# booster.net
KiCad netlist of a schematic drawn in EAGLE
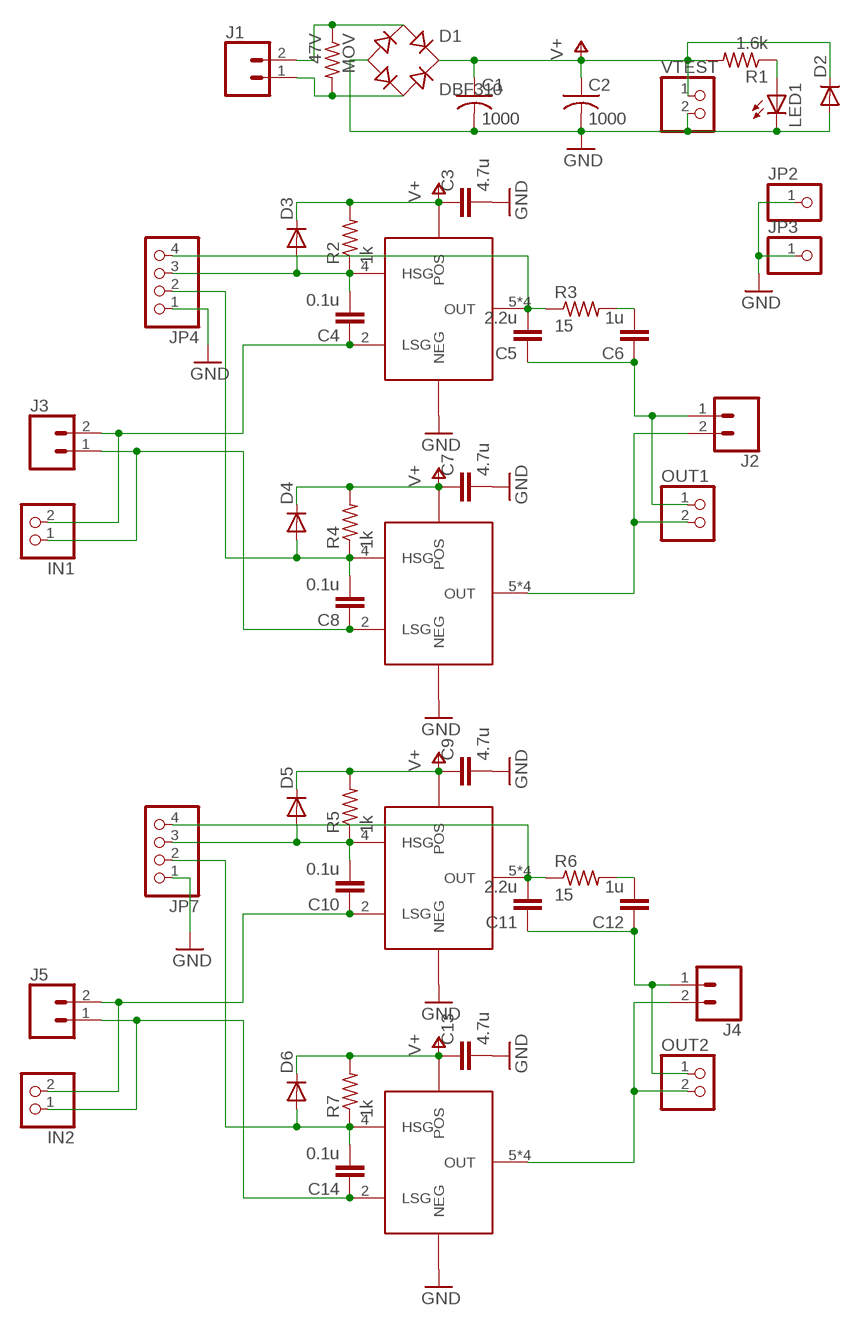
[diagram p0: schematic, sheet 1]

(export (version "E")
  (design (tool "Eeschema 10.0.6"))
  (components
    (comp (ref "C1")
      (value "1000")
      (footprint "eagle-import:CAPPRD500W65D1250H2500B")
      (libsource (lib "eagle-import") (part "UVY1H102MHD"))
    )
    (comp (ref "C2")
      (value "1000")
      (footprint "eagle-import:CAPPRD500W65D1250H2500B")
      (libsource (lib "eagle-import") (part "UVY1H102MHD"))
    )
    (comp (ref "C3")
      (value "4.7u")
      (footprint "eagle-import:C1206")
      (libsource (lib "eagle-import") (part "C-EUC1206"))
    )
    (comp (ref "C4")
      (value "0.1u")
      (footprint "eagle-import:C1206")
      (libsource (lib "eagle-import") (part "C-EUC1206"))
    )
    (comp (ref "C5")
      (value "2.2u")
      (footprint "eagle-import:C1206")
      (libsource (lib "eagle-import") (part "C-EUC1206"))
    )
    (comp (ref "C6")
      (value "1u")
      (footprint "eagle-import:C1206")
      (libsource (lib "eagle-import") (part "C-EUC1206"))
    )
    (comp (ref "C7")
      (value "4.7u")
      (footprint "eagle-import:C1206")
      (libsource (lib "eagle-import") (part "C-EUC1206"))
    )
    (comp (ref "C8")
      (value "0.1u")
      (footprint "eagle-import:C1206")
      (libsource (lib "eagle-import") (part "C-EUC1206"))
    )
    (comp (ref "C9")
      (value "4.7u")
      (footprint "eagle-import:C1206")
      (libsource (lib "eagle-import") (part "C-EUC1206"))
    )
    (comp (ref "C10")
      (value "0.1u")
      (footprint "eagle-import:C1206")
      (libsource (lib "eagle-import") (part "C-EUC1206"))
    )
    (comp (ref "C11")
      (value "2.2u")
      (footprint "eagle-import:C1206")
      (libsource (lib "eagle-import") (part "C-EUC1206"))
    )
    (comp (ref "C12")
      (value "1u")
      (footprint "eagle-import:C1206")
      (libsource (lib "eagle-import") (part "C-EUC1206"))
    )
    (comp (ref "C13")
      (value "4.7u")
      (footprint "eagle-import:C1206")
      (libsource (lib "eagle-import") (part "C-EUC1206"))
    )
    (comp (ref "C14")
      (value "0.1u")
      (footprint "eagle-import:C1206")
      (libsource (lib "eagle-import") (part "C-EUC1206"))
    )
    (comp (ref "D1")
      (value "DBF310")
      (footprint "eagle-import:4-SMD")
      (libsource (lib "eagle-import") (part "DBF310"))
    )
    (comp (ref "D2")
      (value "DIODE-SMB")
      (footprint "eagle-import:SMB")
      (libsource (lib "eagle-import") (part "DIODE-SMB"))
    )
    (comp (ref "D3")
      (value "DIODE-SMB")
      (footprint "eagle-import:SMB")
      (libsource (lib "eagle-import") (part "DIODE-SMB"))
    )
    (comp (ref "D4")
      (value "DIODE-SMB")
      (footprint "eagle-import:SMB")
      (libsource (lib "eagle-import") (part "DIODE-SMB"))
    )
    (comp (ref "D5")
      (value "DIODE-SMB")
      (footprint "eagle-import:SMB")
      (libsource (lib "eagle-import") (part "DIODE-SMB"))
    )
    (comp (ref "D6")
      (value "DIODE-SMB")
      (footprint "eagle-import:SMB")
      (libsource (lib "eagle-import") (part "DIODE-SMB"))
    )
    (comp (ref "IN1")
      (value "PINHD-1X2")
      (footprint "eagle-import:1X02")
      (libsource (lib "eagle-import") (part "PINHD-1X2"))
    )
    (comp (ref "IN2")
      (value "PINHD-1X2")
      (footprint "eagle-import:1X02")
      (libsource (lib "eagle-import") (part "PINHD-1X2"))
    )
    (comp (ref "J1")
      (value "CONN_025MM")
      (footprint "eagle-import:SCREWTERMINAL-5MM-2")
      (libsource (lib "eagle-import") (part "CONN_025MM"))
    )
    (comp (ref "J2")
      (value "CONN_025MM")
      (footprint "eagle-import:SCREWTERMINAL-5MM-2")
      (libsource (lib "eagle-import") (part "CONN_025MM"))
    )
    (comp (ref "J3")
      (value "CONN_025MM")
      (footprint "eagle-import:SCREWTERMINAL-5MM-2")
      (libsource (lib "eagle-import") (part "CONN_025MM"))
    )
    (comp (ref "J4")
      (value "CONN_025MM")
      (footprint "eagle-import:SCREWTERMINAL-5MM-2")
      (libsource (lib "eagle-import") (part "CONN_025MM"))
    )
    (comp (ref "J5")
      (value "CONN_025MM")
      (footprint "eagle-import:SCREWTERMINAL-5MM-2")
      (libsource (lib "eagle-import") (part "CONN_025MM"))
    )
    (comp (ref "JP2")
      (value "PINHD-1X1")
      (footprint "eagle-import:1X01")
      (libsource (lib "eagle-import") (part "PINHD-1X1"))
    )
    (comp (ref "JP3")
      (value "PINHD-1X1")
      (footprint "eagle-import:1X01")
      (libsource (lib "eagle-import") (part "PINHD-1X1"))
    )
    (comp (ref "JP4")
      (value "PINHD-1X4")
      (footprint "eagle-import:1X04")
      (libsource (lib "eagle-import") (part "PINHD-1X4"))
    )
    (comp (ref "JP7")
      (value "PINHD-1X4")
      (footprint "eagle-import:1X04")
      (libsource (lib "eagle-import") (part "PINHD-1X4"))
    )
    (comp (ref "LED1")
      (value "LED5MM")
      (footprint "eagle-import:LED5MM")
      (libsource (lib "eagle-import") (part "LED5MM"))
    )
    (comp (ref "MOV")
      (value "47V")
      (footprint "eagle-import:R1206")
      (libsource (lib "eagle-import") (part "R-US_R1206"))
    )
    (comp (ref "OUT1")
      (value "PINHD-1X2")
      (footprint "eagle-import:1X02")
      (libsource (lib "eagle-import") (part "PINHD-1X2"))
    )
    (comp (ref "OUT2")
      (value "PINHD-1X2")
      (footprint "eagle-import:1X02")
      (libsource (lib "eagle-import") (part "PINHD-1X2"))
    )
    (comp (ref "R1")
      (value "1.6k")
      (footprint "eagle-import:R2512")
      (libsource (lib "eagle-import") (part "R-US_R2512"))
    )
    (comp (ref "R2")
      (value "1k")
      (footprint "eagle-import:R1206")
      (libsource (lib "eagle-import") (part "R-US_R1206"))
    )
    (comp (ref "R3")
      (value "15")
      (footprint "eagle-import:R1206")
      (libsource (lib "eagle-import") (part "R-US_R1206"))
    )
    (comp (ref "R4")
      (value "1k")
      (footprint "eagle-import:R1206")
      (libsource (lib "eagle-import") (part "R-US_R1206"))
    )
    (comp (ref "R5")
      (value "1k")
      (footprint "eagle-import:R1206")
      (libsource (lib "eagle-import") (part "R-US_R1206"))
    )
    (comp (ref "R6")
      (value "15")
      (footprint "eagle-import:R1206")
      (libsource (lib "eagle-import") (part "R-US_R1206"))
    )
    (comp (ref "R7")
      (value "1k")
      (footprint "eagle-import:R1206")
      (libsource (lib "eagle-import") (part "R-US_R1206"))
    )
    (comp (ref "U1")
      (value "SI4554DY")
      (footprint "eagle-import:SOIC-8")
      (libsource (lib "eagle-import") (part "SI4554DY"))
    )
    (comp (ref "U2")
      (value "SI4554DY")
      (footprint "eagle-import:SOIC-8")
      (libsource (lib "eagle-import") (part "SI4554DY"))
    )
    (comp (ref "U3")
      (value "SI4554DY")
      (footprint "eagle-import:SOIC-8")
      (libsource (lib "eagle-import") (part "SI4554DY"))
    )
    (comp (ref "U4")
      (value "SI4554DY")
      (footprint "eagle-import:SOIC-8")
      (libsource (lib "eagle-import") (part "SI4554DY"))
    )
    (comp (ref "VTEST")
      (value "PINHD-1X2")
      (footprint "eagle-import:1X02")
      (libsource (lib "eagle-import") (part "PINHD-1X2"))
    )
  )
  (nets
    (net (code "1") (name "GND") (class "Default")
      (node (ref "C1") (pin "2") (pinfunction "2_2") (pintype "passive"))
      (node (ref "C13") (pin "2") (pinfunction "2_2") (pintype "passive"))
      (node (ref "C2") (pin "2") (pinfunction "2_2") (pintype "passive"))
      (node (ref "C3") (pin "2") (pinfunction "2_2") (pintype "passive"))
      (node (ref "C7") (pin "2") (pinfunction "2_2") (pintype "passive"))
      (node (ref "C9") (pin "2") (pinfunction "2_2") (pintype "passive"))
      (node (ref "D1") (pin "-") (pinfunction "-_-") (pintype "passive"))
      (node (ref "D2") (pin "A") (pinfunction "A_A") (pintype "passive"))
      (node (ref "JP2") (pin "1") (pinfunction "1_1") (pintype "passive"))
      (node (ref "JP3") (pin "1") (pinfunction "1_1") (pintype "passive"))
      (node (ref "JP4") (pin "1") (pinfunction "1_1") (pintype "passive"))
      (node (ref "JP7") (pin "1") (pinfunction "1_1") (pintype "passive"))
      (node (ref "LED1") (pin "K") (pinfunction "C_K") (pintype "passive"))
      (node (ref "U1") (pin "1") (pinfunction "NEG_1") (pintype "bidirectional"))
      (node (ref "U2") (pin "1") (pinfunction "NEG_1") (pintype "bidirectional"))
      (node (ref "U3") (pin "1") (pinfunction "NEG_1") (pintype "bidirectional"))
      (node (ref "U4") (pin "1") (pinfunction "NEG_1") (pintype "bidirectional"))
      (node (ref "VTEST") (pin "2") (pinfunction "2_2") (pintype "passive"))
    )
    (net (code "2") (name "Net-(C5-Pad1)") (class "Default")
      (node (ref "C5") (pin "1") (pinfunction "1_1") (pintype "passive"))
      (node (ref "C6") (pin "1") (pinfunction "1_1") (pintype "passive"))
      (node (ref "J2") (pin "1") (pinfunction "1_1") (pintype "passive"))
      (node (ref "OUT1") (pin "1") (pinfunction "1_1") (pintype "passive"))
    )
    (net (code "3") (name "Net-(C5-Pad2)") (class "Default")
      (node (ref "C5") (pin "2") (pinfunction "2_2") (pintype "passive"))
      (node (ref "JP4") (pin "4") (pinfunction "4_4") (pintype "passive"))
      (node (ref "R3") (pin "1") (pinfunction "1_1") (pintype "passive"))
      (node (ref "U1") (pin "5") (pinfunction "OUT_5") (pintype "bidirectional"))
      (node (ref "U1") (pin "6") (pinfunction "OUT_6") (pintype "bidirectional"))
      (node (ref "U1") (pin "7") (pinfunction "OUT_7") (pintype "bidirectional"))
      (node (ref "U1") (pin "8") (pinfunction "OUT_8") (pintype "bidirectional"))
    )
    (net (code "4") (name "Net-(C6-Pad2)") (class "Default")
      (node (ref "C6") (pin "2") (pinfunction "2_2") (pintype "passive"))
      (node (ref "R3") (pin "2") (pinfunction "2_2") (pintype "passive"))
    )
    (net (code "5") (name "Net-(C11-Pad1)") (class "Default")
      (node (ref "C11") (pin "1") (pinfunction "1_1") (pintype "passive"))
      (node (ref "C12") (pin "1") (pinfunction "1_1") (pintype "passive"))
      (node (ref "J4") (pin "1") (pinfunction "1_1") (pintype "passive"))
      (node (ref "OUT2") (pin "1") (pinfunction "1_1") (pintype "passive"))
    )
    (net (code "6") (name "Net-(C11-Pad2)") (class "Default")
      (node (ref "C11") (pin "2") (pinfunction "2_2") (pintype "passive"))
      (node (ref "JP7") (pin "4") (pinfunction "4_4") (pintype "passive"))
      (node (ref "R6") (pin "1") (pinfunction "1_1") (pintype "passive"))
      (node (ref "U3") (pin "5") (pinfunction "OUT_5") (pintype "bidirectional"))
      (node (ref "U3") (pin "6") (pinfunction "OUT_6") (pintype "bidirectional"))
      (node (ref "U3") (pin "7") (pinfunction "OUT_7") (pintype "bidirectional"))
      (node (ref "U3") (pin "8") (pinfunction "OUT_8") (pintype "bidirectional"))
    )
    (net (code "7") (name "Net-(C12-Pad2)") (class "Default")
      (node (ref "C12") (pin "2") (pinfunction "2_2") (pintype "passive"))
      (node (ref "R6") (pin "2") (pinfunction "2_2") (pintype "passive"))
    )
    (net (code "8") (name "Net-(D1-AC1)") (class "Default")
      (node (ref "D1") (pin "~1") (pinfunction "AC1_~1") (pintype "passive"))
      (node (ref "J1") (pin "2") (pinfunction "2_2") (pintype "passive"))
      (node (ref "MOV") (pin "1") (pinfunction "1_1") (pintype "passive"))
    )
    (net (code "9") (name "Net-(D1-AC2)") (class "Default")
      (node (ref "D1") (pin "~2") (pinfunction "AC2_~2") (pintype "passive"))
      (node (ref "J1") (pin "1") (pinfunction "1_1") (pintype "passive"))
      (node (ref "MOV") (pin "2") (pinfunction "2_2") (pintype "passive"))
    )
    (net (code "10") (name "Net-(J2-Pad2)") (class "Default")
      (node (ref "J2") (pin "2") (pinfunction "2_2") (pintype "passive"))
      (node (ref "OUT1") (pin "2") (pinfunction "2_2") (pintype "passive"))
      (node (ref "U2") (pin "5") (pinfunction "OUT_5") (pintype "bidirectional"))
      (node (ref "U2") (pin "6") (pinfunction "OUT_6") (pintype "bidirectional"))
      (node (ref "U2") (pin "7") (pinfunction "OUT_7") (pintype "bidirectional"))
      (node (ref "U2") (pin "8") (pinfunction "OUT_8") (pintype "bidirectional"))
    )
    (net (code "11") (name "Net-(J4-Pad2)") (class "Default")
      (node (ref "J4") (pin "2") (pinfunction "2_2") (pintype "passive"))
      (node (ref "OUT2") (pin "2") (pinfunction "2_2") (pintype "passive"))
      (node (ref "U4") (pin "5") (pinfunction "OUT_5") (pintype "bidirectional"))
      (node (ref "U4") (pin "6") (pinfunction "OUT_6") (pintype "bidirectional"))
      (node (ref "U4") (pin "7") (pinfunction "OUT_7") (pintype "bidirectional"))
      (node (ref "U4") (pin "8") (pinfunction "OUT_8") (pintype "bidirectional"))
    )
    (net (code "12") (name "Net-(LED1-PadA)") (class "Default")
      (node (ref "LED1") (pin "A") (pinfunction "A_A") (pintype "passive"))
      (node (ref "R1") (pin "1") (pinfunction "1_1") (pintype "passive"))
    )
    (net (code "13") (name "Net-(U1-HSG)") (class "Default")
      (node (ref "C4") (pin "2") (pinfunction "2_2") (pintype "passive"))
      (node (ref "D3") (pin "A") (pinfunction "A_A") (pintype "passive"))
      (node (ref "JP4") (pin "3") (pinfunction "3_3") (pintype "passive"))
      (node (ref "R2") (pin "1") (pinfunction "1_1") (pintype "passive"))
      (node (ref "U1") (pin "4") (pinfunction "HSG_4") (pintype "bidirectional"))
    )
    (net (code "14") (name "Net-(U1-LSG)") (class "Default")
      (node (ref "C4") (pin "1") (pinfunction "1_1") (pintype "passive"))
      (node (ref "IN1") (pin "2") (pinfunction "2_2") (pintype "passive"))
      (node (ref "J3") (pin "2") (pinfunction "2_2") (pintype "passive"))
      (node (ref "U1") (pin "2") (pinfunction "LSG_2") (pintype "bidirectional"))
    )
    (net (code "15") (name "Net-(U2-HSG)") (class "Default")
      (node (ref "C8") (pin "2") (pinfunction "2_2") (pintype "passive"))
      (node (ref "D4") (pin "A") (pinfunction "A_A") (pintype "passive"))
      (node (ref "JP4") (pin "2") (pinfunction "2_2") (pintype "passive"))
      (node (ref "R4") (pin "1") (pinfunction "1_1") (pintype "passive"))
      (node (ref "U2") (pin "4") (pinfunction "HSG_4") (pintype "bidirectional"))
    )
    (net (code "16") (name "Net-(U2-LSG)") (class "Default")
      (node (ref "C8") (pin "1") (pinfunction "1_1") (pintype "passive"))
      (node (ref "IN1") (pin "1") (pinfunction "1_1") (pintype "passive"))
      (node (ref "J3") (pin "1") (pinfunction "1_1") (pintype "passive"))
      (node (ref "U2") (pin "2") (pinfunction "LSG_2") (pintype "bidirectional"))
    )
    (net (code "17") (name "Net-(U3-HSG)") (class "Default")
      (node (ref "C10") (pin "2") (pinfunction "2_2") (pintype "passive"))
      (node (ref "D5") (pin "A") (pinfunction "A_A") (pintype "passive"))
      (node (ref "JP7") (pin "3") (pinfunction "3_3") (pintype "passive"))
      (node (ref "R5") (pin "1") (pinfunction "1_1") (pintype "passive"))
      (node (ref "U3") (pin "4") (pinfunction "HSG_4") (pintype "bidirectional"))
    )
    (net (code "18") (name "Net-(U3-LSG)") (class "Default")
      (node (ref "C10") (pin "1") (pinfunction "1_1") (pintype "passive"))
      (node (ref "IN2") (pin "2") (pinfunction "2_2") (pintype "passive"))
      (node (ref "J5") (pin "2") (pinfunction "2_2") (pintype "passive"))
      (node (ref "U3") (pin "2") (pinfunction "LSG_2") (pintype "bidirectional"))
    )
    (net (code "19") (name "Net-(U4-HSG)") (class "Default")
      (node (ref "C14") (pin "2") (pinfunction "2_2") (pintype "passive"))
      (node (ref "D6") (pin "A") (pinfunction "A_A") (pintype "passive"))
      (node (ref "JP7") (pin "2") (pinfunction "2_2") (pintype "passive"))
      (node (ref "R7") (pin "1") (pinfunction "1_1") (pintype "passive"))
      (node (ref "U4") (pin "4") (pinfunction "HSG_4") (pintype "bidirectional"))
    )
    (net (code "20") (name "Net-(U4-LSG)") (class "Default")
      (node (ref "C14") (pin "1") (pinfunction "1_1") (pintype "passive"))
      (node (ref "IN2") (pin "1") (pinfunction "1_1") (pintype "passive"))
      (node (ref "J5") (pin "1") (pinfunction "1_1") (pintype "passive"))
      (node (ref "U4") (pin "2") (pinfunction "LSG_2") (pintype "bidirectional"))
    )
    (net (code "21") (name "V+") (class "Default")
      (node (ref "C1") (pin "1") (pinfunction "1_1") (pintype "passive"))
      (node (ref "C13") (pin "1") (pinfunction "1_1") (pintype "passive"))
      (node (ref "C2") (pin "1") (pinfunction "1_1") (pintype "passive"))
      (node (ref "C3") (pin "1") (pinfunction "1_1") (pintype "passive"))
      (node (ref "C7") (pin "1") (pinfunction "1_1") (pintype "passive"))
      (node (ref "C9") (pin "1") (pinfunction "1_1") (pintype "passive"))
      (node (ref "D1") (pin "+") (pinfunction "+_+") (pintype "passive"))
      (node (ref "D2") (pin "C") (pinfunction "C_C") (pintype "passive"))
      (node (ref "D3") (pin "C") (pinfunction "C_C") (pintype "passive"))
      (node (ref "D4") (pin "C") (pinfunction "C_C") (pintype "passive"))
      (node (ref "D5") (pin "C") (pinfunction "C_C") (pintype "passive"))
      (node (ref "D6") (pin "C") (pinfunction "C_C") (pintype "passive"))
      (node (ref "R1") (pin "2") (pinfunction "2_2") (pintype "passive"))
      (node (ref "R2") (pin "2") (pinfunction "2_2") (pintype "passive"))
      (node (ref "R4") (pin "2") (pinfunction "2_2") (pintype "passive"))
      (node (ref "R5") (pin "2") (pinfunction "2_2") (pintype "passive"))
      (node (ref "R7") (pin "2") (pinfunction "2_2") (pintype "passive"))
      (node (ref "U1") (pin "3") (pinfunction "POS_3") (pintype "bidirectional"))
      (node (ref "U2") (pin "3") (pinfunction "POS_3") (pintype "bidirectional"))
      (node (ref "U3") (pin "3") (pinfunction "POS_3") (pintype "bidirectional"))
      (node (ref "U4") (pin "3") (pinfunction "POS_3") (pintype "bidirectional"))
      (node (ref "VTEST") (pin "1") (pinfunction "1_1") (pintype "passive"))
    )
  )
)
